# Voltage_Regulators_Backup.net
KiCad netlist of a schematic drawn in Altium Designer
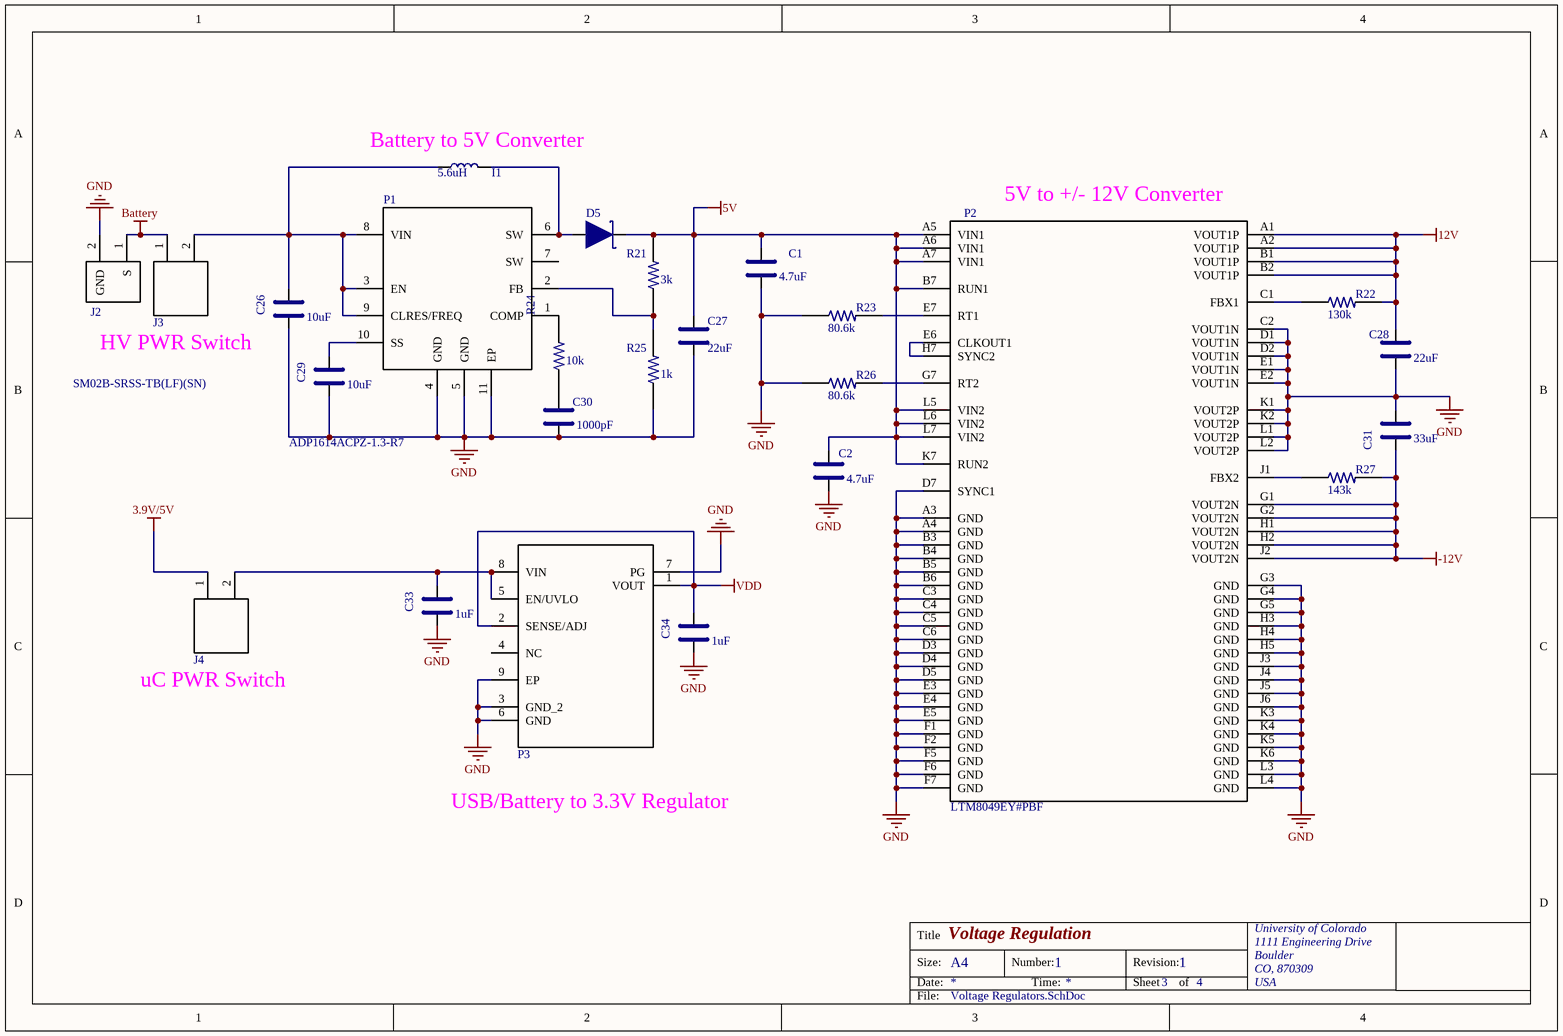
[diagram p0: Voltage Regulators Backup.SchDoc]

(export (version "E")
  (design (tool "Eeschema 10.0.6"))
  (components
    (comp (ref "C1")
      (value "4.7uF")
      (footprint "C0402C102K9RACTU")
      (description "CAP CER 4.7UF 6.3V X5R 0402")
      (fields
        (field (name "MANUFACTURER") "Murata")
        (field (name "MANUFACTURER PART NUMBER") "GRM155R60J475ME47D‎")
      )
      (libsource (lib "Control_Board_Library") (part "GRM155R60J475"))
    )
    (comp (ref "C2")
      (value "4.7uF")
      (footprint "C0402C102K9RACTU")
      (description "CAP CER 4.7UF 6.3V X5R 0402")
      (fields
        (field (name "MANUFACTURER") "Murata")
        (field (name "MANUFACTURER PART NUMBER") "GRM155R60J475ME47D‎")
      )
      (libsource (lib "Control_Board_Library") (part "GRM155R60J475"))
    )
    (comp (ref "C26")
      (value "10uF")
      (footprint "GRM155R60J106ME47D")
      (description "CAP CER 10UF 6.3V X5R 0402")
      (fields
        (field (name "MANUFACTURER") "Murata")
        (field (name "MANUFACTURER PART NUMBER") "GRM155R60J106ME47D")
      )
      (libsource (lib "Control_Board_Library") (part "GRM155R60J106ME47D"))
    )
    (comp (ref "C27")
      (value "22uF")
      (footprint "CC0603MRX5R6BB226")
      (description "CAP CER 22UF 10V X5R 0603")
      (fields
        (field (name "MANUFACTURER") "Yageo")
        (field (name "MANUFACTURER PART NUMBER") "CC0603MRX5R6BB226")
      )
      (libsource (lib "Sensing PEANO_Library") (part "CC0603MRX5R6BB226"))
    )
    (comp (ref "C28")
      (value "22uF")
      (footprint "CL21A226MAQNNNE")
      (description "CAP CER 22UF 25V X5R 0805")
      (fields
        (field (name "MANUFACTURER") "Samsung")
        (field (name "MANUFACTURER PART NUMBER") "CL21A226MAQNNNE")
      )
      (libsource (lib "Sensing PEANO_Library") (part "CL21A226MAQNNNE"))
    )
    (comp (ref "C29")
      (value "10uF")
      (footprint "GRM155R60J106ME47D")
      (description "CAP CER 10UF 6.3V X5R 0402")
      (fields
        (field (name "MANUFACTURER") "Murata")
        (field (name "MANUFACTURER PART NUMBER") "GRM155R60J106ME47D")
      )
      (libsource (lib "Control_Board_Library") (part "GRM155R60J106ME47D"))
    )
    (comp (ref "C30")
      (value "1000pF")
      (footprint "C0402C102K9RACTU")
      (description "CAP CER 1000PF 6.3V X7R 0402")
      (fields
        (field (name "MANUFACTURER") "Murata")
        (field (name "MANUFACTURER PART NUMBER") "GRM155R60J106ME47D")
      )
      (libsource (lib "Sensing PEANO_Library") (part "C0402C102K9RACTU"))
    )
    (comp (ref "C31")
      (value "33uF")
      (footprint "GRM31CR61E476ME44L")
      (description "CAP CER 33UF 25V JB 1206")
      (fields
        (field (name "MANUFACTURER") "TDK Corporation")
        (field (name "MANUFACTURER PART NUMBER") "C3216JB1E336M160AC")
      )
      (libsource (lib "Control_Board_Library") (part "C3216JB1E336M160AC"))
    )
    (comp (ref "C33")
      (value "1uF")
      (footprint "GRM033R60J105MEA2D")
      (description "CAP CER 1UF 6.3V X5R 0201")
      (fields
        (field (name "MANUFACTURER") "Murata")
        (field (name "MANUFACTURER PART NUMBER") "GRM033R60J105MEA2D")
      )
      (libsource (lib "Control_Board_Library") (part "GRM033R60J105MEA2D"))
    )
    (comp (ref "C34")
      (value "1uF")
      (footprint "GRM033R60J105MEA2D")
      (description "CAP CER 1UF 6.3V X5R 0201")
      (fields
        (field (name "MANUFACTURER") "Murata")
        (field (name "MANUFACTURER PART NUMBER") "GRM033R60J105MEA2D")
      )
      (libsource (lib "Control_Board_Library") (part "GRM033R60J105MEA2D"))
    )
    (comp (ref "D5")
      (value "CDBA540-HF")
      (footprint "CDBA540-HF")
      (fields
        (field (name "MANUFACTURER") "Comchip Technology")
        (field (name "DIGIKEY PART NUMBER") "641-1707-1-ND")
      )
      (libsource (lib "Sensing PEANO_Library") (part "CDBA540-HF"))
    )
    (comp (ref "I1")
      (value "5.6uH")
      (footprint "SRP6060FA-5R6M")
      (description "IND,6.6X6.4X5.8MM,5.6UH,20%,10A")
      (fields
        (field (name "MANUFACTURER") "Bourns")
        (field (name "MANUFACTURER PART NUMBER") "SRP6060FA-5R6M")
      )
      (libsource (lib "Sensing PEANO_Library") (part "SRP6060FA-5R6M"))
    )
    (comp (ref "J2")
      (value "SM02B-SRSS-TB(LF)(SN)")
      (footprint "SM02B-SRSS-TB(LF)(SN)")
      (description "SH Series 2 Position 1 mm Pitch Surface Mount Side Entry Shrouded Header")
      (fields (field (name "MP") "SM02B-SRSS-TB_LF__SN_") (field (name "MF") "JST"))
      (libsource (lib "Control_Board_Library") (part "SM02B-SRSS-TB(LF)(SN)"))
    )
    (comp (ref "J3")
      (value "BM02B-SRSS-TBT")
      (footprint "BM02B-SRSS-TBT")
      (description "CONN WIRE HDR 2POS 1MM STSMD")
      (fields (field (name "MANUFACTURER") "JST") (field (name "DIGIKEY PART NUMBER") "455-2955-1-ND"))
      (libsource (lib "Sensing PEANO_Library") (part "BM02B-SRSS-TBT"))
    )
    (comp (ref "J4")
      (value "BM02B-SRSS-TBT")
      (footprint "BM02B-SRSS-TBT")
      (description "CONN WIRE HDR 2POS 1MM STSMD")
      (fields (field (name "MANUFACTURER") "JST") (field (name "DIGIKEY PART NUMBER") "455-2955-1-ND"))
      (libsource (lib "Sensing PEANO_Library") (part "BM02B-SRSS-TBT"))
    )
    (comp (ref "P1")
      (value "ADP1614ACPZ-1.3-R7")
      (footprint "ADP1614ACPZ-1.3-R7")
      (description "IC REG BOOST ADJ 4A 10LFCSP")
      (fields
        (field (name "MANUFACTURER") "Analog Devices")
        (field (name "DIGIKEY PART NUMBER") "ADP1614ACPZ-1.3-R7CT-ND")
      )
      (libsource (lib "Sensing PEANO_Library") (part "ADP1614ACPZ-1.3-R7"))
    )
    (comp (ref "P2")
      (value "LTM8049EY#PBF")
      (footprint "LTM8049EY#PBF")
      (description "DC DC CONVERTER +/-2.5 TO +/-24V")
      (fields
        (field (name "DIGIKEY PART NUMBER") "LTM8049EY#PBF-ND")
        (field (name "MANUFACTURER") "Linear Technology")
      )
      (libsource (lib "Sensing PEANO_Library") (part "LTM8049EY#PBF"))
    )
    (comp (ref "P3")
      (value "ADP7104ACPZ-3.3-R7")
      (footprint "ADP7104ARDZ-3.3")
      (description "IC REG LINEAR 3.3V 500MA 8LFCSP")
      (fields
        (field (name "MANUFACTURER") "Analog Devices")
        (field (name "DIGIKEY PART NUMBER") "ADP7104ACPZ-3.3-R7DKR-ND")
      )
      (libsource (lib "Control_Board_Library") (part "ADP7104ACPZ-3.3-R7"))
    )
    (comp (ref "R21")
      (value "3k")
      (footprint "RC0603F202CS")
      (description "RES 3K OHM 1% 1/20W 0201")
      (fields
        (field (name "MANUFACTURER") "Stackpole")
        (field (name "MANUFACTURER PART NUMBER") "RMCF0201FT3K00")
      )
      (libsource (lib "Sensing PEANO_Library") (part "RMCF0201FT3K00"))
    )
    (comp (ref "R22")
      (value "130k")
      (footprint "RC0201FR-07130KL")
      (description "RES SMD 130K OHM 1% 1/20W 0201")
      (fields
        (field (name "MANUFACTURER") "Yageo")
        (field (name "MANUFACTURER PART NUMBER") "RC0201FR-07130KL")
      )
      (libsource (lib "Sensing PEANO_Library") (part "RC0201FR-07130KL"))
    )
    (comp (ref "R23")
      (value "80.6k")
      (footprint "RC0201FR-0780K6L")
      (description "RES SMD 80.6K OHM 1% 1/20W 0201")
      (fields
        (field (name "MANUFACTURER") "Yageo")
        (field (name "MANUFACTURER PART NUMBER") "RC0201FR-0780K6L")
      )
      (libsource (lib "Sensing PEANO_Library") (part "RC0201FR-0780K6L"))
    )
    (comp (ref "R24")
      (value "10k")
      (footprint "RC0603F103CS")
      (description "RES SMD 10K OHM 1% 1/20W 0201")
      (fields
        (field (name "MANUFACTURER") "Samsung")
        (field (name "MANUFACTURER PART NUMBER") "RC0603F103CS")
      )
      (libsource (lib "Control_Board_Library") (part "RC0603F103CS"))
    )
    (comp (ref "R25")
      (value "1k")
      (footprint "RC0603F202CS")
      (description "RES SMD 1K OHM 1% 1/20W 0201")
      (fields
        (field (name "MANUFACTURER") "Yageo")
        (field (name "MANUFACTURER PART NUMBER") "RC0201FR-071KL")
      )
      (libsource (lib "Sensing PEANO_Library") (part "RC0201FR-071KL"))
    )
    (comp (ref "R26")
      (value "80.6k")
      (footprint "RC0201FR-0780K6L")
      (description "RES SMD 80.6K OHM 1% 1/20W 0201")
      (fields
        (field (name "MANUFACTURER") "Yageo")
        (field (name "MANUFACTURER PART NUMBER") "RC0201FR-0780K6L")
      )
      (libsource (lib "Sensing PEANO_Library") (part "RC0201FR-0780K6L"))
    )
    (comp (ref "R27")
      (value "143k")
      (footprint "RC0201FR-07143KL")
      (description "RES SMD 143K OHM 1% 1/20W 0201")
      (fields
        (field (name "MANUFACTURER") "Yageo")
        (field (name "MANUFACTURER PART NUMBER") "RC0201FR-07143KL")
      )
      (libsource (lib "Sensing PEANO_Library") (part "RC0201FR-07143KL"))
    )
  )
  (nets
    (net (code "1") (name "-12V") (class "Default")
      (node (ref "C31") (pin "2") (pinfunction "2_2") (pintype "passive"))
      (node (ref "P2") (pin "G1") (pinfunction "VOUT2N_G1") (pintype "passive"))
      (node (ref "P2") (pin "G2") (pinfunction "VOUT2N_G2") (pintype "passive"))
      (node (ref "P2") (pin "H1") (pinfunction "VOUT2N_H1") (pintype "passive"))
      (node (ref "P2") (pin "H2") (pinfunction "VOUT2N_H2") (pintype "passive"))
      (node (ref "P2") (pin "J2") (pinfunction "VOUT2N_J2") (pintype "passive"))
      (node (ref "R27") (pin "1") (pinfunction "1_1") (pintype "passive"))
    )
    (net (code "2") (name "3.9V{slash}5V") (class "Default")
      (node (ref "J4") (pin "1") (pinfunction "1_1") (pintype "passive"))
    )
    (net (code "3") (name "5V") (class "Default")
      (node (ref "C1") (pin "1") (pinfunction "1_1") (pintype "passive"))
      (node (ref "C2") (pin "1") (pinfunction "1_1") (pintype "passive"))
      (node (ref "C27") (pin "1") (pinfunction "1_1") (pintype "passive"))
      (node (ref "D5") (pin "1") (pinfunction "1_1") (pintype "passive"))
      (node (ref "P2") (pin "A5") (pinfunction "VIN1_A5") (pintype "passive"))
      (node (ref "P2") (pin "A6") (pinfunction "VIN1_A6") (pintype "passive"))
      (node (ref "P2") (pin "A7") (pinfunction "VIN1_A7") (pintype "passive"))
      (node (ref "P2") (pin "B7") (pinfunction "RUN1_B7") (pintype "passive"))
      (node (ref "P2") (pin "K7") (pinfunction "RUN2_K7") (pintype "passive"))
      (node (ref "P2") (pin "L5") (pinfunction "VIN2_L5") (pintype "passive"))
      (node (ref "P2") (pin "L6") (pinfunction "VIN2_L6") (pintype "passive"))
      (node (ref "P2") (pin "L7") (pinfunction "VIN2_L7") (pintype "passive"))
      (node (ref "R21") (pin "1") (pinfunction "1_1") (pintype "passive"))
    )
    (net (code "4") (name "12V") (class "Default")
      (node (ref "C28") (pin "1") (pinfunction "1_1") (pintype "passive"))
      (node (ref "P2") (pin "A1") (pinfunction "VOUT1P_A1") (pintype "passive"))
      (node (ref "P2") (pin "A2") (pinfunction "VOUT1P_A2") (pintype "passive"))
      (node (ref "P2") (pin "B1") (pinfunction "VOUT1P_B1") (pintype "passive"))
      (node (ref "P2") (pin "B2") (pinfunction "VOUT1P_B2") (pintype "passive"))
      (node (ref "R22") (pin "1") (pinfunction "1_1") (pintype "passive"))
    )
    (net (code "5") (name "Battery") (class "Default")
      (node (ref "J2") (pin "1") (pinfunction "S_1") (pintype "passive"))
      (node (ref "J3") (pin "1") (pinfunction "1_1") (pintype "passive"))
    )
    (net (code "6") (name "GND") (class "Default")
      (node (ref "C1") (pin "2") (pinfunction "2_2") (pintype "passive"))
      (node (ref "C2") (pin "2") (pinfunction "2_2") (pintype "passive"))
      (node (ref "C26") (pin "2") (pinfunction "2_2") (pintype "passive"))
      (node (ref "C27") (pin "2") (pinfunction "2_2") (pintype "passive"))
      (node (ref "C28") (pin "2") (pinfunction "2_2") (pintype "passive"))
      (node (ref "C29") (pin "2") (pinfunction "2_2") (pintype "passive"))
      (node (ref "C30") (pin "2") (pinfunction "2_2") (pintype "passive"))
      (node (ref "C31") (pin "1") (pinfunction "1_1") (pintype "passive"))
      (node (ref "C33") (pin "2") (pinfunction "2_2") (pintype "passive"))
      (node (ref "C34") (pin "2") (pinfunction "2_2") (pintype "passive"))
      (node (ref "J2") (pin "2") (pinfunction "GND_2") (pintype "passive"))
      (node (ref "P1") (pin "11") (pinfunction "EP_11") (pintype "passive"))
      (node (ref "P1") (pin "4") (pinfunction "GND_4") (pintype "passive"))
      (node (ref "P1") (pin "5") (pinfunction "GND_5") (pintype "passive"))
      (node (ref "P2") (pin "A3") (pinfunction "GND_A3") (pintype "passive"))
      (node (ref "P2") (pin "A4") (pinfunction "GND_A4") (pintype "passive"))
      (node (ref "P2") (pin "B3") (pinfunction "GND_B3") (pintype "passive"))
      (node (ref "P2") (pin "B4") (pinfunction "GND_B4") (pintype "passive"))
      (node (ref "P2") (pin "B5") (pinfunction "GND_B5") (pintype "passive"))
      (node (ref "P2") (pin "B6") (pinfunction "GND_B6") (pintype "passive"))
      (node (ref "P2") (pin "C2") (pinfunction "VOUT1N_C2") (pintype "passive"))
      (node (ref "P2") (pin "C3") (pinfunction "GND_C3") (pintype "passive"))
      (node (ref "P2") (pin "C4") (pinfunction "GND_C4") (pintype "passive"))
      (node (ref "P2") (pin "C5") (pinfunction "GND_C5") (pintype "passive"))
      (node (ref "P2") (pin "C6") (pinfunction "GND_C6") (pintype "passive"))
      (node (ref "P2") (pin "D1") (pinfunction "VOUT1N_D1") (pintype "passive"))
      (node (ref "P2") (pin "D2") (pinfunction "VOUT1N_D2") (pintype "passive"))
      (node (ref "P2") (pin "D3") (pinfunction "GND_D3") (pintype "passive"))
      (node (ref "P2") (pin "D4") (pinfunction "GND_D4") (pintype "passive"))
      (node (ref "P2") (pin "D5") (pinfunction "GND_D5") (pintype "passive"))
      (node (ref "P2") (pin "D7") (pinfunction "SYNC1_D7") (pintype "passive"))
      (node (ref "P2") (pin "E1") (pinfunction "VOUT1N_E1") (pintype "passive"))
      (node (ref "P2") (pin "E2") (pinfunction "VOUT1N_E2") (pintype "passive"))
      (node (ref "P2") (pin "E3") (pinfunction "GND_E3") (pintype "passive"))
      (node (ref "P2") (pin "E4") (pinfunction "GND_E4") (pintype "passive"))
      (node (ref "P2") (pin "E5") (pinfunction "GND_E5") (pintype "passive"))
      (node (ref "P2") (pin "F1") (pinfunction "GND_F1") (pintype "passive"))
      (node (ref "P2") (pin "F2") (pinfunction "GND_F2") (pintype "passive"))
      (node (ref "P2") (pin "F5") (pinfunction "GND_F5") (pintype "passive"))
      (node (ref "P2") (pin "F6") (pinfunction "GND_F6") (pintype "passive"))
      (node (ref "P2") (pin "F7") (pinfunction "GND_F7") (pintype "passive"))
      (node (ref "P2") (pin "G3") (pinfunction "GND_G3") (pintype "passive"))
      (node (ref "P2") (pin "G4") (pinfunction "GND_G4") (pintype "passive"))
      (node (ref "P2") (pin "G5") (pinfunction "GND_G5") (pintype "passive"))
      (node (ref "P2") (pin "H3") (pinfunction "GND_H3") (pintype "passive"))
      (node (ref "P2") (pin "H4") (pinfunction "GND_H4") (pintype "passive"))
      (node (ref "P2") (pin "H5") (pinfunction "GND_H5") (pintype "passive"))
      (node (ref "P2") (pin "J3") (pinfunction "GND_J3") (pintype "passive"))
      (node (ref "P2") (pin "J4") (pinfunction "GND_J4") (pintype "passive"))
      (node (ref "P2") (pin "J5") (pinfunction "GND_J5") (pintype "passive"))
      (node (ref "P2") (pin "J6") (pinfunction "GND_J6") (pintype "passive"))
      (node (ref "P2") (pin "K1") (pinfunction "VOUT2P_K1") (pintype "passive"))
      (node (ref "P2") (pin "K2") (pinfunction "VOUT2P_K2") (pintype "passive"))
      (node (ref "P2") (pin "K3") (pinfunction "GND_K3") (pintype "passive"))
      (node (ref "P2") (pin "K4") (pinfunction "GND_K4") (pintype "passive"))
      (node (ref "P2") (pin "K5") (pinfunction "GND_K5") (pintype "passive"))
      (node (ref "P2") (pin "K6") (pinfunction "GND_K6") (pintype "passive"))
      (node (ref "P2") (pin "L1") (pinfunction "VOUT2P_L1") (pintype "passive"))
      (node (ref "P2") (pin "L2") (pinfunction "VOUT2P_L2") (pintype "passive"))
      (node (ref "P2") (pin "L3") (pinfunction "GND_L3") (pintype "passive"))
      (node (ref "P2") (pin "L4") (pinfunction "GND_L4") (pintype "passive"))
      (node (ref "P3") (pin "3") (pinfunction "GND_2_3") (pintype "passive"))
      (node (ref "P3") (pin "6") (pinfunction "GND_6") (pintype "passive"))
      (node (ref "P3") (pin "7") (pinfunction "PG_7") (pintype "passive"))
      (node (ref "P3") (pin "9") (pinfunction "EP_9") (pintype "passive"))
      (node (ref "R23") (pin "2") (pinfunction "2_2") (pintype "passive"))
      (node (ref "R25") (pin "2") (pinfunction "2_2") (pintype "passive"))
      (node (ref "R26") (pin "2") (pinfunction "2_2") (pintype "passive"))
    )
    (net (code "7") (name "Net-(C30-Pad1)") (class "Default")
      (node (ref "C30") (pin "1") (pinfunction "1_1") (pintype "passive"))
      (node (ref "R24") (pin "2") (pinfunction "2_2") (pintype "passive"))
    )
    (net (code "8") (name "Net-(D5-Pad2)") (class "Default")
      (node (ref "D5") (pin "2") (pinfunction "2_2") (pintype "passive"))
      (node (ref "I1") (pin "2") (pinfunction "2_2") (pintype "passive"))
      (node (ref "P1") (pin "6") (pinfunction "SW_6") (pintype "passive"))
    )
    (net (code "9") (name "Net-(P1-CLRES{slash}FREQ)") (class "Default")
      (node (ref "C26") (pin "1") (pinfunction "1_1") (pintype "passive"))
      (node (ref "I1") (pin "1") (pinfunction "1_1") (pintype "passive"))
      (node (ref "J3") (pin "2") (pinfunction "2_2") (pintype "passive"))
      (node (ref "P1") (pin "3") (pinfunction "EN_3") (pintype "passive"))
      (node (ref "P1") (pin "8") (pinfunction "VIN_8") (pintype "passive"))
      (node (ref "P1") (pin "9") (pinfunction "CLRES/FREQ_9") (pintype "passive"))
    )
    (net (code "10") (name "Net-(P1-COMP)") (class "Default")
      (node (ref "P1") (pin "1") (pinfunction "COMP_1") (pintype "passive"))
      (node (ref "R24") (pin "1") (pinfunction "1_1") (pintype "passive"))
    )
    (net (code "11") (name "Net-(P1-FB)") (class "Default")
      (node (ref "P1") (pin "2") (pinfunction "FB_2") (pintype "passive"))
      (node (ref "R21") (pin "2") (pinfunction "2_2") (pintype "passive"))
      (node (ref "R25") (pin "1") (pinfunction "1_1") (pintype "passive"))
    )
    (net (code "12") (name "Net-(P1-SS)") (class "Default")
      (node (ref "C29") (pin "1") (pinfunction "1_1") (pintype "passive"))
      (node (ref "P1") (pin "10") (pinfunction "SS_10") (pintype "passive"))
    )
    (net (code "13") (name "Net-(P2-CLKOUT1)") (class "Default")
      (node (ref "P2") (pin "E6") (pinfunction "CLKOUT1_E6") (pintype "passive"))
      (node (ref "P2") (pin "H7") (pinfunction "SYNC2_H7") (pintype "passive"))
    )
    (net (code "14") (name "Net-(P2-FBX1)") (class "Default")
      (node (ref "P2") (pin "C1") (pinfunction "FBX1_C1") (pintype "passive"))
      (node (ref "R22") (pin "2") (pinfunction "2_2") (pintype "passive"))
    )
    (net (code "15") (name "Net-(P2-FBX2)") (class "Default")
      (node (ref "P2") (pin "J1") (pinfunction "FBX2_J1") (pintype "passive"))
      (node (ref "R27") (pin "2") (pinfunction "2_2") (pintype "passive"))
    )
    (net (code "16") (name "Net-(P2-RT1)") (class "Default")
      (node (ref "P2") (pin "E7") (pinfunction "RT1_E7") (pintype "passive"))
      (node (ref "R23") (pin "1") (pinfunction "1_1") (pintype "passive"))
    )
    (net (code "17") (name "Net-(P2-RT2)") (class "Default")
      (node (ref "P2") (pin "G7") (pinfunction "RT2_G7") (pintype "passive"))
      (node (ref "R26") (pin "1") (pinfunction "1_1") (pintype "passive"))
    )
    (net (code "18") (name "Net-(P3-EN{slash}UVLO)") (class "Default")
      (node (ref "C33") (pin "1") (pinfunction "1_1") (pintype "passive"))
      (node (ref "J4") (pin "2") (pinfunction "2_2") (pintype "passive"))
      (node (ref "P3") (pin "5") (pinfunction "EN/UVLO_5") (pintype "passive"))
      (node (ref "P3") (pin "8") (pinfunction "VIN_8") (pintype "passive"))
    )
    (net (code "19") (name "VDD") (class "Default")
      (node (ref "C34") (pin "1") (pinfunction "1_1") (pintype "passive"))
      (node (ref "P3") (pin "1") (pinfunction "VOUT_1") (pintype "passive"))
      (node (ref "P3") (pin "2") (pinfunction "SENSE/ADJ_2") (pintype "passive"))
    )
    (net (code "20") (name "unconnected-(P1-SW-Pad7)") (class "Default")
      (node (ref "P1") (pin "7") (pinfunction "SW_7") (pintype "passive"))
    )
    (net (code "21") (name "unconnected-(P3-NC-Pad4)") (class "Default")
      (node (ref "P3") (pin "4") (pinfunction "NC_4") (pintype "passive"))
    )
  )
)
